# ETH_on_RS485_Node_Example_Mikrocontrolle.net
KiCad netlist of a schematic drawn in Altium Designer
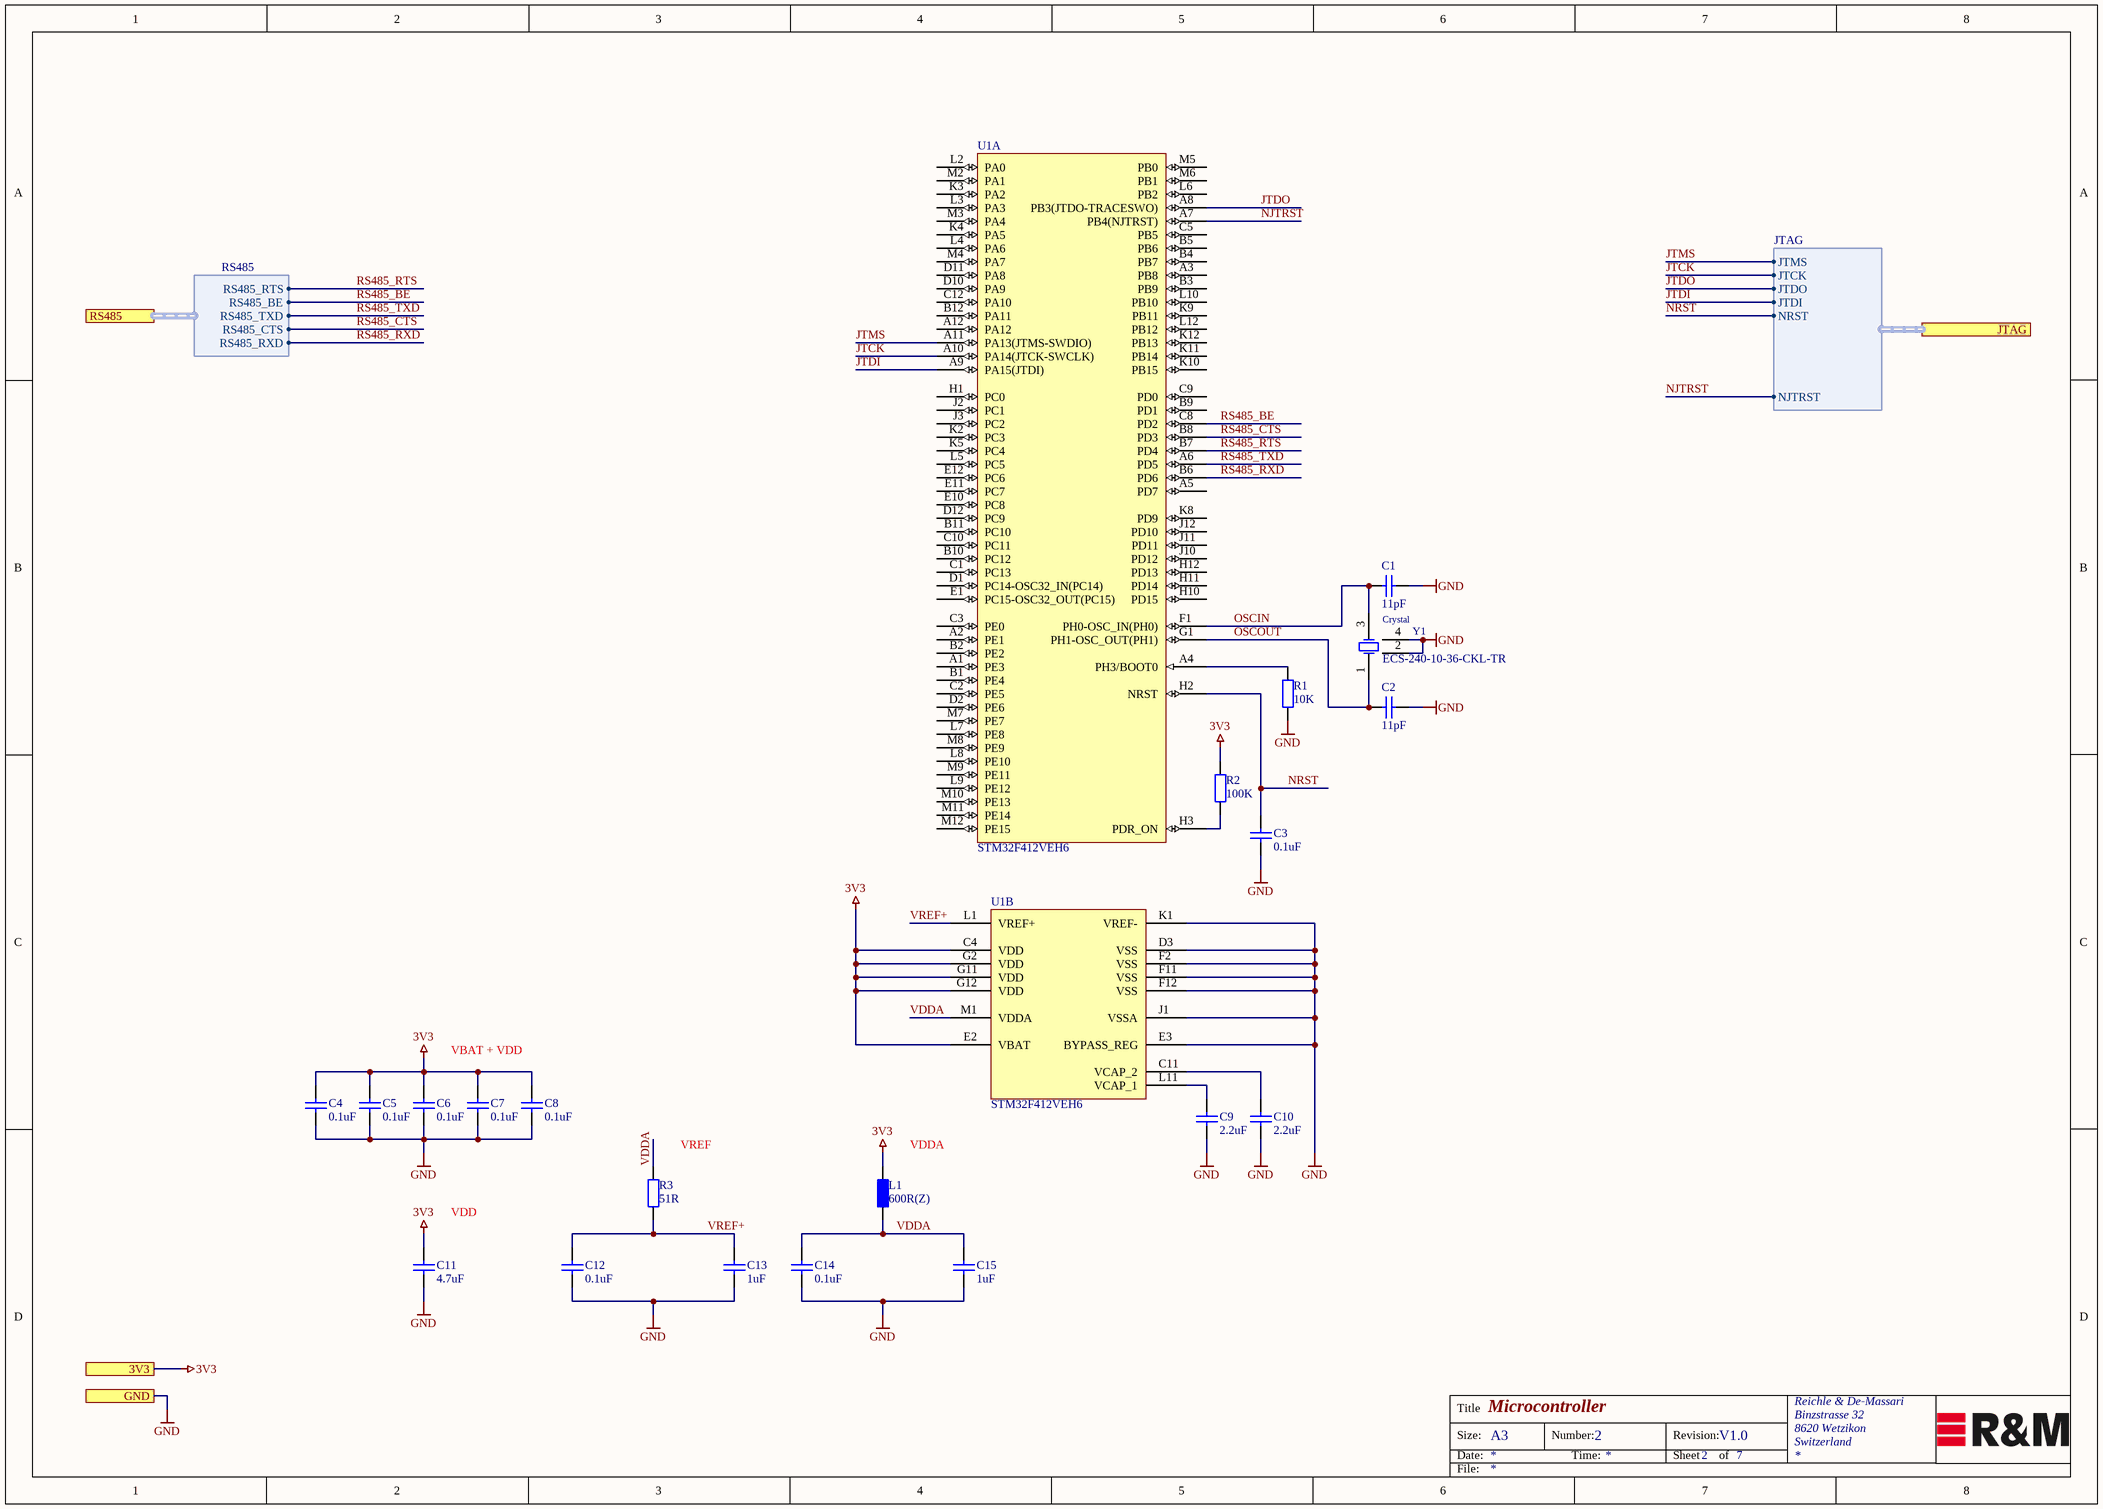
[diagram p0: ETH_on_RS485_Node_Example_Mikrocontroller.SchDoc]

(export (version "E")
  (design (tool "Eeschema 10.0.6"))
  (components
    (comp (ref "C1")
      (value "11pF")
      (footprint "Ceramic Capacitor 0402 EIA")
      (description "SMD/SMT 0402 11pF 50volts C0G 5%")
      (fields (field (name "TOLERANCE") "5%") (field (name "VOLTAGE") "50VDC"))
      (libsource (lib "RDM_Altium_Library") (part "Cap_11pF_0402"))
    )
    (comp (ref "C2")
      (value "11pF")
      (footprint "Ceramic Capacitor 0402 EIA")
      (description "SMD/SMT 0402 11pF 50volts C0G 5%")
      (fields (field (name "TOLERANCE") "5%") (field (name "VOLTAGE") "50VDC"))
      (libsource (lib "RDM_Altium_Library") (part "Cap_11pF_0402"))
    )
    (comp (ref "C3")
      (value "0.1uF")
      (footprint "Ceramic Capacitor 0402 EIA")
      (description "SMD/SMT WCAP-CSGP 0.1uF 0402 20% 10V MLCC")
      (fields (field (name "TOLERANCE") "20%") (field (name "VOLTAGE") "10VDC"))
      (libsource (lib "RDM_Altium_Library") (part "Cap_0.1uF_0402"))
    )
    (comp (ref "C4")
      (value "0.1uF")
      (footprint "Ceramic Capacitor 0402 EIA")
      (description "SMD/SMT WCAP-CSGP 0.1uF 0402 20% 10V MLCC")
      (fields (field (name "TOLERANCE") "20%") (field (name "VOLTAGE") "10VDC"))
      (libsource (lib "RDM_Altium_Library") (part "Cap_0.1uF_0402"))
    )
    (comp (ref "C5")
      (value "0.1uF")
      (footprint "Ceramic Capacitor 0402 EIA")
      (description "SMD/SMT WCAP-CSGP 0.1uF 0402 20% 10V MLCC")
      (fields (field (name "TOLERANCE") "20%") (field (name "VOLTAGE") "10VDC"))
      (libsource (lib "RDM_Altium_Library") (part "Cap_0.1uF_0402"))
    )
    (comp (ref "C6")
      (value "0.1uF")
      (footprint "Ceramic Capacitor 0402 EIA")
      (description "SMD/SMT WCAP-CSGP 0.1uF 0402 20% 10V MLCC")
      (fields (field (name "TOLERANCE") "20%") (field (name "VOLTAGE") "10VDC"))
      (libsource (lib "RDM_Altium_Library") (part "Cap_0.1uF_0402"))
    )
    (comp (ref "C7")
      (value "0.1uF")
      (footprint "Ceramic Capacitor 0402 EIA")
      (description "SMD/SMT WCAP-CSGP 0.1uF 0402 20% 10V MLCC")
      (fields (field (name "TOLERANCE") "20%") (field (name "VOLTAGE") "10VDC"))
      (libsource (lib "RDM_Altium_Library") (part "Cap_0.1uF_0402"))
    )
    (comp (ref "C8")
      (value "0.1uF")
      (footprint "Ceramic Capacitor 0402 EIA")
      (description "SMD/SMT WCAP-CSGP 0.1uF 0402 20% 10V MLCC")
      (fields (field (name "TOLERANCE") "20%") (field (name "VOLTAGE") "10VDC"))
      (libsource (lib "RDM_Altium_Library") (part "Cap_0.1uF_0402"))
    )
    (comp (ref "C9")
      (value "2.2uF")
      (footprint "Ceramic Capacitor 0402 EIA")
      (description "2.2µF ±20% 25V Ceramic Capacitor X5R 0402 (1005 Metric)")
      (fields (field (name "TOLERANCE") "±20%") (field (name "VOLTAGE") "25V"))
      (libsource (lib "RDM_Altium_Library") (part "Cap_2.2uF_0402"))
    )
    (comp (ref "C10")
      (value "2.2uF")
      (footprint "Ceramic Capacitor 0402 EIA")
      (description "2.2µF ±20% 25V Ceramic Capacitor X5R 0402 (1005 Metric)")
      (fields (field (name "TOLERANCE") "±20%") (field (name "VOLTAGE") "25V"))
      (libsource (lib "RDM_Altium_Library") (part "Cap_2.2uF_0402"))
    )
    (comp (ref "C11")
      (value "4.7uF")
      (footprint "Ceramic Capacitor 0603 EIA")
      (description "SMD/SMT 0603 4.7uF 10volts")
      (fields (field (name "TOLERANCE") "20%") (field (name "VOLTAGE") "10VDC"))
      (libsource (lib "RDM_Altium_Library") (part "Cap_4.7uF_0603"))
    )
    (comp (ref "C12")
      (value "0.1uF")
      (footprint "Ceramic Capacitor 0402 EIA")
      (description "SMD/SMT WCAP-CSGP 0.1uF 0402 20% 10V MLCC")
      (fields (field (name "TOLERANCE") "20%") (field (name "VOLTAGE") "10VDC"))
      (libsource (lib "RDM_Altium_Library") (part "Cap_0.1uF_0402"))
    )
    (comp (ref "C13")
      (value "1uF")
      (footprint "Ceramic Capacitor 0402 EIA")
      (description "SMD/SMT 0402 1uF 10volts X7S 10%")
      (fields (field (name "TOLERANCE") "10%") (field (name "VOLTAGE") "10VDC"))
      (libsource (lib "RDM_Altium_Library") (part "Cap_1uF_0402"))
    )
    (comp (ref "C14")
      (value "0.1uF")
      (footprint "Ceramic Capacitor 0402 EIA")
      (description "SMD/SMT WCAP-CSGP 0.1uF 0402 20% 10V MLCC")
      (fields (field (name "TOLERANCE") "20%") (field (name "VOLTAGE") "10VDC"))
      (libsource (lib "RDM_Altium_Library") (part "Cap_0.1uF_0402"))
    )
    (comp (ref "C15")
      (value "1uF")
      (footprint "Ceramic Capacitor 0402 EIA")
      (description "SMD/SMT 0402 1uF 10volts X7S 10%")
      (fields (field (name "TOLERANCE") "10%") (field (name "VOLTAGE") "10VDC"))
      (libsource (lib "RDM_Altium_Library") (part "Cap_1uF_0402"))
    )
    (comp (ref "L1")
      (value "600R(Z)")
      (footprint "Inductor 0603 EIA")
      (description "Ferritperlen MULTILYR CHP BD 0603 600OHMS 25%")
      (fields (field (name "TOLERANCE") "25%") (field (name "MANUFACTURER") "Taiyo Yuden"))
      (libsource (lib "RDM_ALT_SCH") (part "Ind_600R_0603"))
    )
    (comp (ref "R1")
      (value "10K")
      (footprint "Resistor 0402 EIA")
      (description "SMD 10K ohm 1% 50V General Purpose")
      (fields (field (name "TOLERANCE") "1%") (field (name "POWER") "63mW"))
      (libsource (lib "RDM_Altium_Library") (part "Res_10K_0402"))
    )
    (comp (ref "R2")
      (value "100K")
      (footprint "Resistor 0402 EIA")
      (description "100 kOhm Resistor 0402")
      (fields (field (name "POWER") "63mW") (field (name "MANUFACTURER") "Vishay"))
      (libsource (lib "RDM_ALT_SCH") (part "Res_100K_0402"))
    )
    (comp (ref "R3")
      (value "51R")
      (footprint "Resistor 0402 EIA")
      (description "Resistor")
      (fields (field (name "TOLERANCE") "5%") (field (name "POWER") "62.5mW"))
      (libsource (lib "RDM_ALT_SCH") (part "Res_51R_0402"))
    )
    (comp (ref "U1")
      (value "STM32F412VEH6")
      (footprint "STM_UFBGA100 7x7x0.6_100_R")
      (fields (field (name "MANUFACTURER") "STM"))
      (libsource (lib "RDM_ALT_SCH") (part "STM_STM32F412VEH6_UFBGA100 7x7x0.6_100_1"))
    )
    (comp (ref "Y1")
      (value "Crystal")
      (footprint "ECS_ECX-2236_4_R")
      (description "Quarze 24MHz 10pF 10ppm -10C +70C")
      (fields (field (name "MANUFACTURER PARTNR") "ECS-240-10-36-CKL-TR"))
      (libsource (lib "RDM_ALT_SCH") (part "ECS-240-10-36-CKL-TR"))
    )
  )
  (nets
    (net (code "3") (name "/JTCK") (class "Default")
      (node (ref "U1") (pin "A10") (pinfunction "PA14(JTCK-SWCLK)_A10") (pintype "bidirectional"))
    )
    (net (code "4") (name "/JTDI") (class "Default")
      (node (ref "U1") (pin "A9") (pinfunction "PA15(JTDI)_A9") (pintype "bidirectional"))
    )
    (net (code "5") (name "/JTDO") (class "Default")
      (node (ref "U1") (pin "A8") (pinfunction "PB3(JTDO-TRACESWO)_A8") (pintype "bidirectional"))
    )
    (net (code "6") (name "/JTMS") (class "Default")
      (node (ref "U1") (pin "A11") (pinfunction "PA13(JTMS-SWDIO)_A11") (pintype "bidirectional"))
    )
    (net (code "7") (name "/NJTRST") (class "Default")
      (node (ref "U1") (pin "A7") (pinfunction "PB4(NJTRST)_A7") (pintype "bidirectional"))
    )
    (net (code "8") (name "/NRST") (class "Default")
      (node (ref "C3") (pin "1") (pinfunction "1_1") (pintype "passive"))
      (node (ref "U1") (pin "H2") (pinfunction "NRST_H2") (pintype "bidirectional"))
    )
    (net (code "9") (name "/OSCIN") (class "Default")
      (node (ref "C1") (pin "1") (pinfunction "1_1") (pintype "passive"))
      (node (ref "U1") (pin "F1") (pinfunction "PH0-OSC_IN(PH0)_F1") (pintype "bidirectional"))
      (node (ref "Y1") (pin "3") (pinfunction "OSC2_3") (pintype "passive"))
    )
    (net (code "10") (name "/OSCOUT") (class "Default")
      (node (ref "C2") (pin "1") (pinfunction "1_1") (pintype "passive"))
      (node (ref "U1") (pin "G1") (pinfunction "PH1-OSC_OUT(PH1)_G1") (pintype "bidirectional"))
      (node (ref "Y1") (pin "1") (pinfunction "OSC1_1") (pintype "passive"))
    )
    (net (code "11") (name "/RS485_BE") (class "Default")
      (node (ref "U1") (pin "C8") (pinfunction "PD2_C8") (pintype "bidirectional"))
    )
    (net (code "12") (name "/RS485_CTS") (class "Default")
      (node (ref "U1") (pin "B8") (pinfunction "PD3_B8") (pintype "bidirectional"))
    )
    (net (code "13") (name "/RS485_RTS") (class "Default")
      (node (ref "U1") (pin "B7") (pinfunction "PD4_B7") (pintype "bidirectional"))
    )
    (net (code "14") (name "/RS485_RXD") (class "Default")
      (node (ref "U1") (pin "B6") (pinfunction "PD6_B6") (pintype "bidirectional"))
    )
    (net (code "15") (name "/RS485_TXD") (class "Default")
      (node (ref "U1") (pin "A6") (pinfunction "PD5_A6") (pintype "bidirectional"))
    )
    (net (code "16") (name "/VDDA") (class "Default")
      (node (ref "C14") (pin "2") (pinfunction "2_2") (pintype "passive"))
      (node (ref "C15") (pin "2") (pinfunction "2_2") (pintype "passive"))
      (node (ref "L1") (pin "2") (pinfunction "2_2") (pintype "passive"))
      (node (ref "R3") (pin "2") (pinfunction "2_2") (pintype "passive"))
      (node (ref "U1") (pin "M1") (pinfunction "VDDA_M1") (pintype "power_in"))
    )
    (net (code "17") (name "/VREF+") (class "Default")
      (node (ref "C12") (pin "2") (pinfunction "2_2") (pintype "passive"))
      (node (ref "C13") (pin "2") (pinfunction "2_2") (pintype "passive"))
      (node (ref "R3") (pin "1") (pinfunction "1_1") (pintype "passive"))
      (node (ref "U1") (pin "L1") (pinfunction "VREF+_L1") (pintype "power_in"))
    )
    (net (code "20") (name "3V3") (class "Default")
      (node (ref "C11") (pin "2") (pinfunction "2_2") (pintype "passive"))
      (node (ref "C4") (pin "1") (pinfunction "1_1") (pintype "passive"))
      (node (ref "C5") (pin "1") (pinfunction "1_1") (pintype "passive"))
      (node (ref "C6") (pin "1") (pinfunction "1_1") (pintype "passive"))
      (node (ref "C7") (pin "1") (pinfunction "1_1") (pintype "passive"))
      (node (ref "C8") (pin "1") (pinfunction "1_1") (pintype "passive"))
      (node (ref "L1") (pin "1") (pinfunction "1_1") (pintype "passive"))
      (node (ref "R2") (pin "2") (pinfunction "2_2") (pintype "passive"))
      (node (ref "U1") (pin "C4") (pinfunction "VDD_C4") (pintype "power_in"))
      (node (ref "U1") (pin "E2") (pinfunction "VBAT_E2") (pintype "power_in"))
      (node (ref "U1") (pin "G11") (pinfunction "VDD_G11") (pintype "power_in"))
      (node (ref "U1") (pin "G12") (pinfunction "VDD_G12") (pintype "power_in"))
      (node (ref "U1") (pin "G2") (pinfunction "VDD_G2") (pintype "power_in"))
    )
    (net (code "21") (name "GND") (class "Default")
      (node (ref "C1") (pin "2") (pinfunction "2_2") (pintype "passive"))
      (node (ref "C10") (pin "1") (pinfunction "1_1") (pintype "passive"))
      (node (ref "C11") (pin "1") (pinfunction "1_1") (pintype "passive"))
      (node (ref "C12") (pin "1") (pinfunction "1_1") (pintype "passive"))
      (node (ref "C13") (pin "1") (pinfunction "1_1") (pintype "passive"))
      (node (ref "C14") (pin "1") (pinfunction "1_1") (pintype "passive"))
      (node (ref "C15") (pin "1") (pinfunction "1_1") (pintype "passive"))
      (node (ref "C2") (pin "2") (pinfunction "2_2") (pintype "passive"))
      (node (ref "C3") (pin "2") (pinfunction "2_2") (pintype "passive"))
      (node (ref "C4") (pin "2") (pinfunction "2_2") (pintype "passive"))
      (node (ref "C5") (pin "2") (pinfunction "2_2") (pintype "passive"))
      (node (ref "C6") (pin "2") (pinfunction "2_2") (pintype "passive"))
      (node (ref "C7") (pin "2") (pinfunction "2_2") (pintype "passive"))
      (node (ref "C8") (pin "2") (pinfunction "2_2") (pintype "passive"))
      (node (ref "C9") (pin "1") (pinfunction "1_1") (pintype "passive"))
      (node (ref "R1") (pin "1") (pinfunction "1_1") (pintype "passive"))
      (node (ref "U1") (pin "D3") (pinfunction "VSS_D3") (pintype "power_in"))
      (node (ref "U1") (pin "E3") (pinfunction "BYPASS_REG_E3") (pintype "power_in"))
      (node (ref "U1") (pin "F11") (pinfunction "VSS_F11") (pintype "power_in"))
      (node (ref "U1") (pin "F12") (pinfunction "VSS_F12") (pintype "power_in"))
      (node (ref "U1") (pin "F2") (pinfunction "VSS_F2") (pintype "power_in"))
      (node (ref "U1") (pin "J1") (pinfunction "VSSA_J1") (pintype "power_in"))
      (node (ref "U1") (pin "K1") (pinfunction "VREF-_K1") (pintype "power_in"))
      (node (ref "Y1") (pin "2") (pinfunction "OSC2_2") (pintype "passive"))
      (node (ref "Y1") (pin "4") (pinfunction "OSC3_4") (pintype "passive"))
    )
    (net (code "22") (name "Net-(U1A-PDR_ON)") (class "Default")
      (node (ref "R2") (pin "1") (pinfunction "1_1") (pintype "passive"))
      (node (ref "U1") (pin "H3") (pinfunction "PDR_ON_H3") (pintype "bidirectional"))
    )
    (net (code "23") (name "Net-(U1A-PH3{slash}BOOT0)") (class "Default")
      (node (ref "R1") (pin "2") (pinfunction "2_2") (pintype "passive"))
      (node (ref "U1") (pin "A4") (pinfunction "PH3/BOOT0_A4") (pintype "input"))
    )
    (net (code "24") (name "Net-(U1B-VCAP_1)") (class "Default")
      (node (ref "C9") (pin "2") (pinfunction "2_2") (pintype "passive"))
      (node (ref "U1") (pin "L11") (pinfunction "VCAP_1_L11") (pintype "power_in"))
    )
    (net (code "25") (name "Net-(U1B-VCAP_2)") (class "Default")
      (node (ref "C10") (pin "2") (pinfunction "2_2") (pintype "passive"))
      (node (ref "U1") (pin "C11") (pinfunction "VCAP_2_C11") (pintype "power_in"))
    )
    (net (code "26") (name "unconnected-(U1A-PA0-PadL2)") (class "Default")
      (node (ref "U1") (pin "L2") (pinfunction "PA0_L2") (pintype "bidirectional"))
    )
    (net (code "27") (name "unconnected-(U1A-PA1-PadM2)") (class "Default")
      (node (ref "U1") (pin "M2") (pinfunction "PA1_M2") (pintype "bidirectional"))
    )
    (net (code "28") (name "unconnected-(U1A-PA2-PadK3)") (class "Default")
      (node (ref "U1") (pin "K3") (pinfunction "PA2_K3") (pintype "bidirectional"))
    )
    (net (code "29") (name "unconnected-(U1A-PA3-PadL3)") (class "Default")
      (node (ref "U1") (pin "L3") (pinfunction "PA3_L3") (pintype "bidirectional"))
    )
    (net (code "30") (name "unconnected-(U1A-PA4-PadM3)") (class "Default")
      (node (ref "U1") (pin "M3") (pinfunction "PA4_M3") (pintype "bidirectional"))
    )
    (net (code "31") (name "unconnected-(U1A-PA5-PadK4)") (class "Default")
      (node (ref "U1") (pin "K4") (pinfunction "PA5_K4") (pintype "bidirectional"))
    )
    (net (code "32") (name "unconnected-(U1A-PA6-PadL4)") (class "Default")
      (node (ref "U1") (pin "L4") (pinfunction "PA6_L4") (pintype "bidirectional"))
    )
    (net (code "33") (name "unconnected-(U1A-PA7-PadM4)") (class "Default")
      (node (ref "U1") (pin "M4") (pinfunction "PA7_M4") (pintype "bidirectional"))
    )
    (net (code "34") (name "unconnected-(U1A-PA8-PadD11)") (class "Default")
      (node (ref "U1") (pin "D11") (pinfunction "PA8_D11") (pintype "bidirectional"))
    )
    (net (code "35") (name "unconnected-(U1A-PA9-PadD10)") (class "Default")
      (node (ref "U1") (pin "D10") (pinfunction "PA9_D10") (pintype "bidirectional"))
    )
    (net (code "36") (name "unconnected-(U1A-PA10-PadC12)") (class "Default")
      (node (ref "U1") (pin "C12") (pinfunction "PA10_C12") (pintype "bidirectional"))
    )
    (net (code "37") (name "unconnected-(U1A-PA11-PadB12)") (class "Default")
      (node (ref "U1") (pin "B12") (pinfunction "PA11_B12") (pintype "bidirectional"))
    )
    (net (code "38") (name "unconnected-(U1A-PA12-PadA12)") (class "Default")
      (node (ref "U1") (pin "A12") (pinfunction "PA12_A12") (pintype "bidirectional"))
    )
    (net (code "39") (name "unconnected-(U1A-PB0-PadM5)") (class "Default")
      (node (ref "U1") (pin "M5") (pinfunction "PB0_M5") (pintype "bidirectional"))
    )
    (net (code "40") (name "unconnected-(U1A-PB1-PadM6)") (class "Default")
      (node (ref "U1") (pin "M6") (pinfunction "PB1_M6") (pintype "bidirectional"))
    )
    (net (code "41") (name "unconnected-(U1A-PB2-PadL6)") (class "Default")
      (node (ref "U1") (pin "L6") (pinfunction "PB2_L6") (pintype "bidirectional"))
    )
    (net (code "42") (name "unconnected-(U1A-PB5-PadC5)") (class "Default")
      (node (ref "U1") (pin "C5") (pinfunction "PB5_C5") (pintype "bidirectional"))
    )
    (net (code "43") (name "unconnected-(U1A-PB6-PadB5)") (class "Default")
      (node (ref "U1") (pin "B5") (pinfunction "PB6_B5") (pintype "bidirectional"))
    )
    (net (code "44") (name "unconnected-(U1A-PB7-PadB4)") (class "Default")
      (node (ref "U1") (pin "B4") (pinfunction "PB7_B4") (pintype "bidirectional"))
    )
    (net (code "45") (name "unconnected-(U1A-PB8-PadA3)") (class "Default")
      (node (ref "U1") (pin "A3") (pinfunction "PB8_A3") (pintype "bidirectional"))
    )
    (net (code "46") (name "unconnected-(U1A-PB9-PadB3)") (class "Default")
      (node (ref "U1") (pin "B3") (pinfunction "PB9_B3") (pintype "bidirectional"))
    )
    (net (code "47") (name "unconnected-(U1A-PB10-PadL10)") (class "Default")
      (node (ref "U1") (pin "L10") (pinfunction "PB10_L10") (pintype "bidirectional"))
    )
    (net (code "48") (name "unconnected-(U1A-PB11-PadK9)") (class "Default")
      (node (ref "U1") (pin "K9") (pinfunction "PB11_K9") (pintype "bidirectional"))
    )
    (net (code "49") (name "unconnected-(U1A-PB12-PadL12)") (class "Default")
      (node (ref "U1") (pin "L12") (pinfunction "PB12_L12") (pintype "bidirectional"))
    )
    (net (code "50") (name "unconnected-(U1A-PB13-PadK12)") (class "Default")
      (node (ref "U1") (pin "K12") (pinfunction "PB13_K12") (pintype "bidirectional"))
    )
    (net (code "51") (name "unconnected-(U1A-PB14-PadK11)") (class "Default")
      (node (ref "U1") (pin "K11") (pinfunction "PB14_K11") (pintype "bidirectional"))
    )
    (net (code "52") (name "unconnected-(U1A-PB15-PadK10)") (class "Default")
      (node (ref "U1") (pin "K10") (pinfunction "PB15_K10") (pintype "bidirectional"))
    )
    (net (code "53") (name "unconnected-(U1A-PC0-PadH1)") (class "Default")
      (node (ref "U1") (pin "H1") (pinfunction "PC0_H1") (pintype "bidirectional"))
    )
    (net (code "54") (name "unconnected-(U1A-PC1-PadJ2)") (class "Default")
      (node (ref "U1") (pin "J2") (pinfunction "PC1_J2") (pintype "bidirectional"))
    )
    (net (code "55") (name "unconnected-(U1A-PC2-PadJ3)") (class "Default")
      (node (ref "U1") (pin "J3") (pinfunction "PC2_J3") (pintype "bidirectional"))
    )
    (net (code "56") (name "unconnected-(U1A-PC3-PadK2)") (class "Default")
      (node (ref "U1") (pin "K2") (pinfunction "PC3_K2") (pintype "bidirectional"))
    )
    (net (code "57") (name "unconnected-(U1A-PC4-PadK5)") (class "Default")
      (node (ref "U1") (pin "K5") (pinfunction "PC4_K5") (pintype "bidirectional"))
    )
    (net (code "58") (name "unconnected-(U1A-PC5-PadL5)") (class "Default")
      (node (ref "U1") (pin "L5") (pinfunction "PC5_L5") (pintype "bidirectional"))
    )
    (net (code "59") (name "unconnected-(U1A-PC6-PadE12)") (class "Default")
      (node (ref "U1") (pin "E12") (pinfunction "PC6_E12") (pintype "bidirectional"))
    )
    (net (code "60") (name "unconnected-(U1A-PC7-PadE11)") (class "Default")
      (node (ref "U1") (pin "E11") (pinfunction "PC7_E11") (pintype "bidirectional"))
    )
    (net (code "61") (name "unconnected-(U1A-PC8-PadE10)") (class "Default")
      (node (ref "U1") (pin "E10") (pinfunction "PC8_E10") (pintype "bidirectional"))
    )
    (net (code "62") (name "unconnected-(U1A-PC9-PadD12)") (class "Default")
      (node (ref "U1") (pin "D12") (pinfunction "PC9_D12") (pintype "bidirectional"))
    )
    (net (code "63") (name "unconnected-(U1A-PC10-PadB11)") (class "Default")
      (node (ref "U1") (pin "B11") (pinfunction "PC10_B11") (pintype "bidirectional"))
    )
    (net (code "64") (name "unconnected-(U1A-PC11-PadC10)") (class "Default")
      (node (ref "U1") (pin "C10") (pinfunction "PC11_C10") (pintype "bidirectional"))
    )
    (net (code "65") (name "unconnected-(U1A-PC12-PadB10)") (class "Default")
      (node (ref "U1") (pin "B10") (pinfunction "PC12_B10") (pintype "bidirectional"))
    )
    (net (code "66") (name "unconnected-(U1A-PC13-PadC1)") (class "Default")
      (node (ref "U1") (pin "C1") (pinfunction "PC13_C1") (pintype "bidirectional"))
    )
    (net (code "67") (name "unconnected-(U1A-PC14-OSC32_IN(PC14)-PadD1)") (class "Default")
      (node (ref "U1") (pin "D1") (pinfunction "PC14-OSC32_IN(PC14)_D1") (pintype "bidirectional"))
    )
    (net (code "68") (name "unconnected-(U1A-PC15-OSC32_OUT(PC15)-PadE1)") (class "Default")
      (node (ref "U1") (pin "E1") (pinfunction "PC15-OSC32_OUT(PC15)_E1") (pintype "bidirectional"))
    )
    (net (code "69") (name "unconnected-(U1A-PD0-PadC9)") (class "Default")
      (node (ref "U1") (pin "C9") (pinfunction "PD0_C9") (pintype "bidirectional"))
    )
    (net (code "70") (name "unconnected-(U1A-PD1-PadB9)") (class "Default")
      (node (ref "U1") (pin "B9") (pinfunction "PD1_B9") (pintype "bidirectional"))
    )
    (net (code "71") (name "unconnected-(U1A-PD7-PadA5)") (class "Default")
      (node (ref "U1") (pin "A5") (pinfunction "PD7_A5") (pintype "bidirectional"))
    )
    (net (code "72") (name "unconnected-(U1A-PD9-PadK8)") (class "Default")
      (node (ref "U1") (pin "K8") (pinfunction "PD9_K8") (pintype "bidirectional"))
    )
    (net (code "73") (name "unconnected-(U1A-PD10-PadJ12)") (class "Default")
      (node (ref "U1") (pin "J12") (pinfunction "PD10_J12") (pintype "bidirectional"))
    )
    (net (code "74") (name "unconnected-(U1A-PD11-PadJ11)") (class "Default")
      (node (ref "U1") (pin "J11") (pinfunction "PD11_J11") (pintype "bidirectional"))
    )
    (net (code "75") (name "unconnected-(U1A-PD12-PadJ10)") (class "Default")
      (node (ref "U1") (pin "J10") (pinfunction "PD12_J10") (pintype "bidirectional"))
    )
    (net (code "76") (name "unconnected-(U1A-PD13-PadH12)") (class "Default")
      (node (ref "U1") (pin "H12") (pinfunction "PD13_H12") (pintype "bidirectional"))
    )
    (net (code "77") (name "unconnected-(U1A-PD14-PadH11)") (class "Default")
      (node (ref "U1") (pin "H11") (pinfunction "PD14_H11") (pintype "bidirectional"))
    )
    (net (code "78") (name "unconnected-(U1A-PD15-PadH10)") (class "Default")
      (node (ref "U1") (pin "H10") (pinfunction "PD15_H10") (pintype "bidirectional"))
    )
    (net (code "79") (name "unconnected-(U1A-PE0-PadC3)") (class "Default")
      (node (ref "U1") (pin "C3") (pinfunction "PE0_C3") (pintype "bidirectional"))
    )
    (net (code "80") (name "unconnected-(U1A-PE1-PadA2)") (class "Default")
      (node (ref "U1") (pin "A2") (pinfunction "PE1_A2") (pintype "bidirectional"))
    )
    (net (code "81") (name "unconnected-(U1A-PE2-PadB2)") (class "Default")
      (node (ref "U1") (pin "B2") (pinfunction "PE2_B2") (pintype "bidirectional"))
    )
    (net (code "82") (name "unconnected-(U1A-PE3-PadA1)") (class "Default")
      (node (ref "U1") (pin "A1") (pinfunction "PE3_A1") (pintype "bidirectional"))
    )
    (net (code "83") (name "unconnected-(U1A-PE4-PadB1)") (class "Default")
      (node (ref "U1") (pin "B1") (pinfunction "PE4_B1") (pintype "bidirectional"))
    )
    (net (code "84") (name "unconnected-(U1A-PE5-PadC2)") (class "Default")
      (node (ref "U1") (pin "C2") (pinfunction "PE5_C2") (pintype "bidirectional"))
    )
    (net (code "85") (name "unconnected-(U1A-PE6-PadD2)") (class "Default")
      (node (ref "U1") (pin "D2") (pinfunction "PE6_D2") (pintype "bidirectional"))
    )
    (net (code "86") (name "unconnected-(U1A-PE7-PadM7)") (class "Default")
      (node (ref "U1") (pin "M7") (pinfunction "PE7_M7") (pintype "bidirectional"))
    )
    (net (code "87") (name "unconnected-(U1A-PE8-PadL7)") (class "Default")
      (node (ref "U1") (pin "L7") (pinfunction "PE8_L7") (pintype "bidirectional"))
    )
    (net (code "88") (name "unconnected-(U1A-PE9-PadM8)") (class "Default")
      (node (ref "U1") (pin "M8") (pinfunction "PE9_M8") (pintype "bidirectional"))
    )
    (net (code "89") (name "unconnected-(U1A-PE10-PadL8)") (class "Default")
      (node (ref "U1") (pin "L8") (pinfunction "PE10_L8") (pintype "bidirectional"))
    )
    (net (code "90") (name "unconnected-(U1A-PE11-PadM9)") (class "Default")
      (node (ref "U1") (pin "M9") (pinfunction "PE11_M9") (pintype "bidirectional"))
    )
    (net (code "91") (name "unconnected-(U1A-PE12-PadL9)") (class "Default")
      (node (ref "U1") (pin "L9") (pinfunction "PE12_L9") (pintype "bidirectional"))
    )
    (net (code "92") (name "unconnected-(U1A-PE13-PadM10)") (class "Default")
      (node (ref "U1") (pin "M10") (pinfunction "PE13_M10") (pintype "bidirectional"))
    )
    (net (code "93") (name "unconnected-(U1A-PE14-PadM11)") (class "Default")
      (node (ref "U1") (pin "M11") (pinfunction "PE14_M11") (pintype "bidirectional"))
    )
    (net (code "94") (name "unconnected-(U1A-PE15-PadM12)") (class "Default")
      (node (ref "U1") (pin "M12") (pinfunction "PE15_M12") (pintype "bidirectional"))
    )
  )
)
